# Outputs.net
KiCad netlist of a schematic drawn in Altium Designer
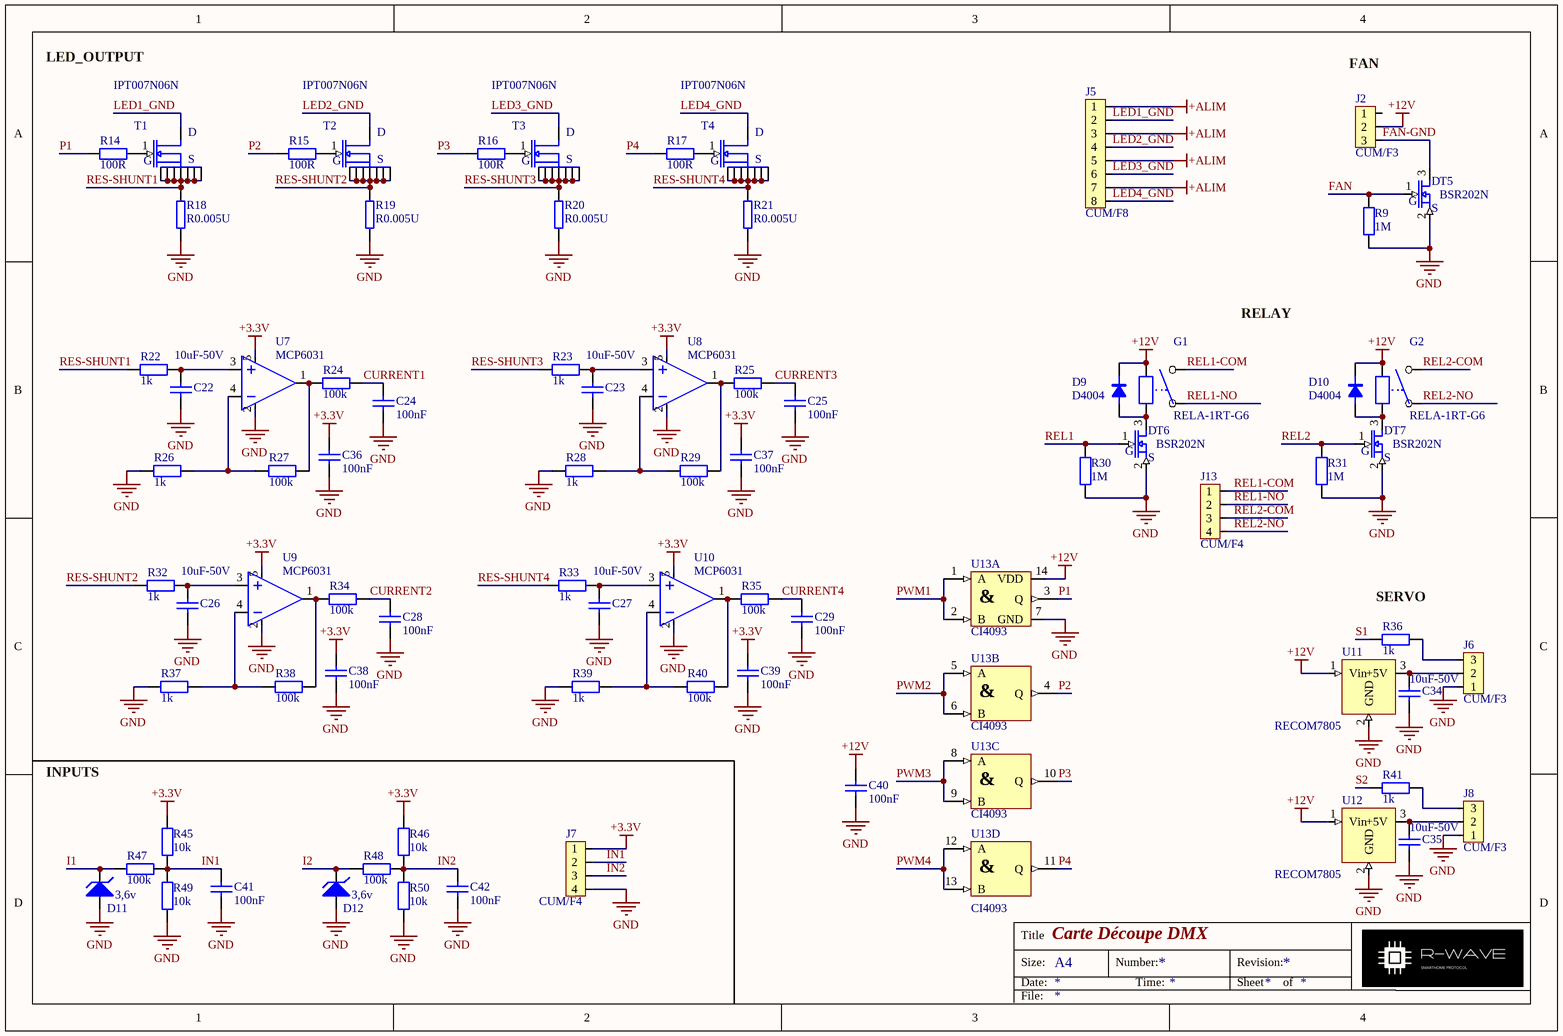
[diagram p0: Outputs.SchDoc]

(export (version "E")
  (design (tool "Eeschema 10.0.6"))
  (components
    (comp (ref "C22")
      (value "10uF-50V")
      (footprint "C1206")
      (description "Capacitor")
      (libsource (lib "MyLibrary") (part "Cap"))
    )
    (comp (ref "C23")
      (value "10uF-50V")
      (footprint "C1206")
      (description "Capacitor")
      (libsource (lib "MyLibrary") (part "Cap"))
    )
    (comp (ref "C24")
      (value "100nF")
      (footprint "C0603")
      (description "Capacitor")
      (libsource (lib "MyLibrary") (part "Cap"))
    )
    (comp (ref "C25")
      (value "100nF")
      (footprint "C0603")
      (description "Capacitor")
      (libsource (lib "MyLibrary") (part "Cap"))
    )
    (comp (ref "C26")
      (value "10uF-50V")
      (footprint "C1206")
      (description "Capacitor")
      (libsource (lib "MyLibrary") (part "Cap"))
    )
    (comp (ref "C27")
      (value "10uF-50V")
      (footprint "C1206")
      (description "Capacitor")
      (libsource (lib "MyLibrary") (part "Cap"))
    )
    (comp (ref "C28")
      (value "100nF")
      (footprint "C0603")
      (description "Capacitor")
      (libsource (lib "MyLibrary") (part "Cap"))
    )
    (comp (ref "C29")
      (value "100nF")
      (footprint "C0603")
      (description "Capacitor")
      (libsource (lib "MyLibrary") (part "Cap"))
    )
    (comp (ref "C34")
      (value "10uF-50V")
      (footprint "C1206")
      (description "Capacitor")
      (libsource (lib "MyLibrary") (part "Cap"))
    )
    (comp (ref "C35")
      (value "10uF-50V")
      (footprint "C1206")
      (description "Capacitor")
      (libsource (lib "MyLibrary") (part "Cap"))
    )
    (comp (ref "C36")
      (value "100nF")
      (footprint "C0603")
      (description "Capacitor")
      (libsource (lib "MyLibrary") (part "Cap"))
    )
    (comp (ref "C37")
      (value "100nF")
      (footprint "C0603")
      (description "Capacitor")
      (libsource (lib "MyLibrary") (part "Cap"))
    )
    (comp (ref "C38")
      (value "100nF")
      (footprint "C0603")
      (description "Capacitor")
      (libsource (lib "MyLibrary") (part "Cap"))
    )
    (comp (ref "C39")
      (value "100nF")
      (footprint "C0603")
      (description "Capacitor")
      (libsource (lib "MyLibrary") (part "Cap"))
    )
    (comp (ref "C40")
      (value "100nF")
      (footprint "C0603")
      (description "Capacitor")
      (libsource (lib "MyLibrary") (part "Cap"))
    )
    (comp (ref "C41")
      (value "100nF")
      (footprint "C0603")
      (description "Capacitor")
      (libsource (lib "MyLibrary") (part "Cap"))
    )
    (comp (ref "C42")
      (value "100nF")
      (footprint "C0603")
      (description "Capacitor")
      (libsource (lib "MyLibrary") (part "Cap"))
    )
    (comp (ref "D9")
      (value "D4004")
      (footprint "DIO4004A")
      (description "DIODE CMS 1A 400V  boitier DO214AC")
      (libsource (lib "PROTEL") (part "D4004"))
    )
    (comp (ref "D10")
      (value "D4004")
      (footprint "DIO4004A")
      (description "DIODE CMS 1A 400V  boitier DO214AC")
      (libsource (lib "PROTEL") (part "D4004"))
    )
    (comp (ref "D11")
      (value "3,6v")
      (footprint "SOD123")
      (description "Zener Diode")
      (libsource (lib "MyLibrary") (part "D Zener"))
    )
    (comp (ref "D12")
      (value "3,6v")
      (footprint "SOD123")
      (description "Zener Diode")
      (libsource (lib "MyLibrary") (part "D Zener"))
    )
    (comp (ref "G1")
      (value "RELA-1RT-G6")
      (footprint "RELG6D1A")
      (description "RELAIS 1RT 12V")
      (libsource (lib "PROTEL") (part "RELA-1RT-G6"))
    )
    (comp (ref "G2")
      (value "RELA-1RT-G6")
      (footprint "RELG6D1A")
      (description "RELAIS 1RT 12V")
      (libsource (lib "PROTEL") (part "RELA-1RT-G6"))
    )
    (comp (ref "J2")
      (value "CUM/F3")
      (footprint "HDR1X3")
      (description "connecteur 3 points")
      (libsource (lib "PROTEL") (part "CUM/F3"))
    )
    (comp (ref "J5")
      (value "CUM/F8")
      (footprint "CNT8C3")
      (description "connecteur 8 points")
      (libsource (lib "PROTEL") (part "CUM/F8"))
    )
    (comp (ref "J6")
      (value "CUM/F3")
      (footprint "HDR1X3")
      (description "connecteur 3 points")
      (libsource (lib "") (part "CUM/F3_1"))
    )
    (comp (ref "J7")
      (value "CUM/F4")
      (footprint "CNT4J")
      (description "connecteur  4 points")
      (libsource (lib "PROTEL") (part "CUM/F4"))
    )
    (comp (ref "J8")
      (value "CUM/F3")
      (footprint "HDR1X3")
      (description "connecteur 3 points")
      (libsource (lib "") (part "CUM/F3_1"))
    )
    (comp (ref "J13")
      (value "CUM/F4")
      (footprint "CNT4F0")
      (description "connecteur  4 points")
      (libsource (lib "PROTEL") (part "CUM/F4"))
    )
    (comp (ref "R9")
      (value "1M")
      (footprint "R0603")
      (description "Thin Metal Film Resistor")
      (libsource (lib "") (part "Res_1"))
    )
    (comp (ref "R14")
      (value "100R")
      (footprint "R0603")
      (description "Thin Metal Film Resistor")
      (libsource (lib "") (part "Res_2"))
    )
    (comp (ref "R15")
      (value "100R")
      (footprint "R0603")
      (description "Thin Metal Film Resistor")
      (libsource (lib "") (part "Res_2"))
    )
    (comp (ref "R16")
      (value "100R")
      (footprint "R0603")
      (description "Thin Metal Film Resistor")
      (libsource (lib "") (part "Res_2"))
    )
    (comp (ref "R17")
      (value "100R")
      (footprint "R0603")
      (description "Thin Metal Film Resistor")
      (libsource (lib "") (part "Res_2"))
    )
    (comp (ref "R18")
      (value "R0.005U")
      (footprint "RCER005")
      (description "Resistance 0.005U 1W 1% CMS BOITIER 2512")
      (libsource (lib "PROTEL") (part "R0.005U"))
    )
    (comp (ref "R19")
      (value "R0.005U")
      (footprint "RCER005")
      (description "Resistance 0.005U 1W 1% CMS BOITIER 2512")
      (libsource (lib "PROTEL") (part "R0.005U"))
    )
    (comp (ref "R20")
      (value "R0.005U")
      (footprint "RCER005")
      (description "Resistance 0.005U 1W 1% CMS BOITIER 2512")
      (libsource (lib "PROTEL") (part "R0.005U"))
    )
    (comp (ref "R21")
      (value "R0.005U")
      (footprint "RCER005")
      (description "Resistance 0.005U 1W 1% CMS BOITIER 2512")
      (libsource (lib "PROTEL") (part "R0.005U"))
    )
    (comp (ref "R22")
      (value "1k")
      (footprint "R0603")
      (description "Thin Metal Film Resistor")
      (libsource (lib "") (part "Res_2"))
    )
    (comp (ref "R23")
      (value "1k")
      (footprint "R0603")
      (description "Thin Metal Film Resistor")
      (libsource (lib "") (part "Res_2"))
    )
    (comp (ref "R24")
      (value "100k")
      (footprint "R0603")
      (description "Thin Metal Film Resistor")
      (libsource (lib "") (part "Res_2"))
    )
    (comp (ref "R25")
      (value "100k")
      (footprint "R0603")
      (description "Thin Metal Film Resistor")
      (libsource (lib "") (part "Res_2"))
    )
    (comp (ref "R26")
      (value "1k")
      (footprint "R0603")
      (description "Thin Metal Film Resistor")
      (libsource (lib "") (part "Res_2"))
    )
    (comp (ref "R27")
      (value "100k")
      (footprint "R0603")
      (description "Thin Metal Film Resistor")
      (libsource (lib "") (part "Res_2"))
    )
    (comp (ref "R28")
      (value "1k")
      (footprint "R0603")
      (description "Thin Metal Film Resistor")
      (libsource (lib "") (part "Res_2"))
    )
    (comp (ref "R29")
      (value "100k")
      (footprint "R0603")
      (description "Thin Metal Film Resistor")
      (libsource (lib "") (part "Res_2"))
    )
    (comp (ref "R30")
      (value "1M")
      (footprint "R0603")
      (description "Thin Metal Film Resistor")
      (libsource (lib "") (part "Res_1"))
    )
    (comp (ref "R31")
      (value "1M")
      (footprint "R0603")
      (description "Thin Metal Film Resistor")
      (libsource (lib "") (part "Res_1"))
    )
    (comp (ref "R32")
      (value "1k")
      (footprint "R0603")
      (description "Thin Metal Film Resistor")
      (libsource (lib "") (part "Res_2"))
    )
    (comp (ref "R33")
      (value "1k")
      (footprint "R0603")
      (description "Thin Metal Film Resistor")
      (libsource (lib "") (part "Res_2"))
    )
    (comp (ref "R34")
      (value "100k")
      (footprint "R0603")
      (description "Thin Metal Film Resistor")
      (libsource (lib "") (part "Res_2"))
    )
    (comp (ref "R35")
      (value "100k")
      (footprint "R0603")
      (description "Thin Metal Film Resistor")
      (libsource (lib "") (part "Res_2"))
    )
    (comp (ref "R36")
      (value "1k")
      (footprint "R0603")
      (description "Thin Metal Film Resistor")
      (libsource (lib "") (part "Res_2"))
    )
    (comp (ref "R37")
      (value "1k")
      (footprint "R0603")
      (description "Thin Metal Film Resistor")
      (libsource (lib "") (part "Res_2"))
    )
    (comp (ref "R38")
      (value "100k")
      (footprint "R0603")
      (description "Thin Metal Film Resistor")
      (libsource (lib "") (part "Res_2"))
    )
    (comp (ref "R39")
      (value "1k")
      (footprint "R0603")
      (description "Thin Metal Film Resistor")
      (libsource (lib "") (part "Res_2"))
    )
    (comp (ref "R40")
      (value "100k")
      (footprint "R0603")
      (description "Thin Metal Film Resistor")
      (libsource (lib "") (part "Res_2"))
    )
    (comp (ref "R41")
      (value "1k")
      (footprint "R0603")
      (description "Thin Metal Film Resistor")
      (libsource (lib "") (part "Res_2"))
    )
    (comp (ref "R45")
      (value "10k")
      (footprint "R0603")
      (description "Thin Metal Film Resistor")
      (libsource (lib "MyLibrary") (part "Res"))
    )
    (comp (ref "R46")
      (value "10k")
      (footprint "R0603")
      (description "Thin Metal Film Resistor")
      (libsource (lib "MyLibrary") (part "Res"))
    )
    (comp (ref "R47")
      (value "100k")
      (footprint "R0603")
      (description "Thin Metal Film Resistor")
      (libsource (lib "") (part "Res_2"))
    )
    (comp (ref "R48")
      (value "100k")
      (footprint "R0603")
      (description "Thin Metal Film Resistor")
      (libsource (lib "") (part "Res_2"))
    )
    (comp (ref "R49")
      (value "10k")
      (footprint "R0603")
      (description "Thin Metal Film Resistor")
      (libsource (lib "MyLibrary") (part "Res"))
    )
    (comp (ref "R50")
      (value "10k")
      (footprint "R0603")
      (description "Thin Metal Film Resistor")
      (libsource (lib "MyLibrary") (part "Res"))
    )
    (comp (ref "T1")
      (value "IPT007N06N")
      (footprint "TRA007")
      (description "TRANSISTOR MOS N")
      (libsource (lib "PROTEL") (part "IPT007N06N"))
    )
    (comp (ref "T2")
      (value "IPT007N06N")
      (footprint "TRA007")
      (description "TRANSISTOR MOS N")
      (libsource (lib "PROTEL") (part "IPT007N06N"))
    )
    (comp (ref "T3")
      (value "IPT007N06N")
      (footprint "TRA007")
      (description "TRANSISTOR MOS N")
      (libsource (lib "PROTEL") (part "IPT007N06N"))
    )
    (comp (ref "T4")
      (value "IPT007N06N")
      (footprint "TRA007")
      (description "TRANSISTOR MOS N")
      (libsource (lib "PROTEL") (part "IPT007N06N"))
    )
    (comp (ref "T5")
      (value "BSR202N")
      (footprint "TRA202")
      (description "TRANSISTOR MOS N")
      (libsource (lib "PROTEL") (part "BSR202N"))
    )
    (comp (ref "T6")
      (value "BSR202N")
      (footprint "TRA202")
      (description "TRANSISTOR MOS N")
      (libsource (lib "PROTEL") (part "BSR202N"))
    )
    (comp (ref "T7")
      (value "BSR202N")
      (footprint "TRA202")
      (description "TRANSISTOR MOS N")
      (libsource (lib "PROTEL") (part "BSR202N"))
    )
    (comp (ref "U7")
      (value "MCP6031")
      (footprint "CIA6031")
      (description "SOT23")
      (libsource (lib "PROTEL") (part "MCP6031"))
    )
    (comp (ref "U8")
      (value "MCP6031")
      (footprint "CIA6031")
      (description "SOT23")
      (libsource (lib "PROTEL") (part "MCP6031"))
    )
    (comp (ref "U9")
      (value "MCP6031")
      (footprint "CIA6031")
      (description "SOT23")
      (libsource (lib "PROTEL") (part "MCP6031"))
    )
    (comp (ref "U10")
      (value "MCP6031")
      (footprint "CIA6031")
      (description "SOT23")
      (libsource (lib "PROTEL") (part "MCP6031"))
    )
    (comp (ref "U11")
      (value "RECOM7805")
      (footprint "REG5VG")
      (description "Régulateur à piquer recom")
      (libsource (lib "PROTEL") (part "RECOM7805"))
    )
    (comp (ref "U12")
      (value "RECOM7805")
      (footprint "REG5VG")
      (description "Régulateur à piquer recom")
      (libsource (lib "PROTEL") (part "RECOM7805"))
    )
    (comp (ref "U13")
      (value "CI4093")
      (footprint "CIL4093")
      (description "Quad NAND gate")
      (libsource (lib "PROTEL") (part "CI4093"))
    )
  )
  (nets
    (net (code "1") (name "+3.3V") (class "Default")
      (node (ref "C36") (pin "2") (pinfunction "2_2") (pintype "passive"))
      (node (ref "C37") (pin "2") (pinfunction "2_2") (pintype "passive"))
      (node (ref "C38") (pin "2") (pinfunction "2_2") (pintype "passive"))
      (node (ref "C39") (pin "2") (pinfunction "2_2") (pintype "passive"))
      (node (ref "J7") (pin "1") (pinfunction "1_1") (pintype "passive"))
      (node (ref "R45") (pin "1") (pinfunction "1_1") (pintype "passive"))
      (node (ref "R46") (pin "1") (pinfunction "1_1") (pintype "passive"))
      (node (ref "U10") (pin "5") (pinfunction "VDD_5") (pintype "power_in"))
      (node (ref "U7") (pin "5") (pinfunction "VDD_5") (pintype "power_in"))
      (node (ref "U8") (pin "5") (pinfunction "VDD_5") (pintype "power_in"))
      (node (ref "U9") (pin "5") (pinfunction "VDD_5") (pintype "power_in"))
    )
    (net (code "2") (name "+12V") (class "Default")
      (node (ref "C40") (pin "2") (pinfunction "2_2") (pintype "passive"))
      (node (ref "D10") (pin "1") (pinfunction "1_1") (pintype "passive"))
      (node (ref "D9") (pin "1") (pinfunction "1_1") (pintype "passive"))
      (node (ref "G1") (pin "7") (pintype "passive"))
      (node (ref "G2") (pin "7") (pintype "passive"))
      (node (ref "J2") (pin "2") (pinfunction "2_2") (pintype "passive"))
      (node (ref "U11") (pin "1") (pinfunction "Vin_1") (pintype "input"))
      (node (ref "U12") (pin "1") (pinfunction "Vin_1") (pintype "input"))
      (node (ref "U13") (pin "14") (pinfunction "VDD_14") (pintype "power_in"))
    )
    (net (code "3") (name "+ALIM") (class "Default")
      (node (ref "J5") (pin "1") (pinfunction "1_1") (pintype "passive"))
      (node (ref "J5") (pin "3") (pinfunction "3_3") (pintype "passive"))
      (node (ref "J5") (pin "5") (pinfunction "5_5") (pintype "passive"))
      (node (ref "J5") (pin "7") (pinfunction "7_7") (pintype "passive"))
    )
    (net (code "4") (name "/CURRENT1") (class "Default")
      (node (ref "C24") (pin "1") (pinfunction "1_1") (pintype "passive"))
      (node (ref "R24") (pin "1") (pinfunction "1_1") (pintype "passive"))
    )
    (net (code "5") (name "/CURRENT2") (class "Default")
      (node (ref "C28") (pin "1") (pinfunction "1_1") (pintype "passive"))
      (node (ref "R34") (pin "1") (pinfunction "1_1") (pintype "passive"))
    )
    (net (code "6") (name "/CURRENT3") (class "Default")
      (node (ref "C25") (pin "1") (pinfunction "1_1") (pintype "passive"))
      (node (ref "R25") (pin "1") (pinfunction "1_1") (pintype "passive"))
    )
    (net (code "7") (name "/CURRENT4") (class "Default")
      (node (ref "C29") (pin "1") (pinfunction "1_1") (pintype "passive"))
      (node (ref "R35") (pin "1") (pinfunction "1_1") (pintype "passive"))
    )
    (net (code "8") (name "/FAN") (class "Default")
      (node (ref "R9") (pin "2") (pinfunction "2_2") (pintype "passive"))
      (node (ref "T5") (pin "1") (pinfunction "G_1") (pintype "input"))
    )
    (net (code "9") (name "/FAN-GND") (class "Default")
      (node (ref "J2") (pin "3") (pinfunction "3_3") (pintype "passive"))
      (node (ref "T5") (pin "3") (pinfunction "D_3") (pintype "passive"))
    )
    (net (code "10") (name "/I1") (class "Default")
      (node (ref "D11") (pin "2") (pinfunction "K_2") (pintype "passive"))
      (node (ref "R47") (pin "2") (pinfunction "2_2") (pintype "passive"))
    )
    (net (code "11") (name "/I2") (class "Default")
      (node (ref "D12") (pin "2") (pinfunction "K_2") (pintype "passive"))
      (node (ref "R48") (pin "2") (pinfunction "2_2") (pintype "passive"))
    )
    (net (code "12") (name "/IN1") (class "Default")
      (node (ref "C41") (pin "2") (pinfunction "2_2") (pintype "passive"))
      (node (ref "J7") (pin "2") (pinfunction "2_2") (pintype "passive"))
      (node (ref "R45") (pin "2") (pinfunction "2_2") (pintype "passive"))
      (node (ref "R47") (pin "1") (pinfunction "1_1") (pintype "passive"))
      (node (ref "R49") (pin "1") (pinfunction "1_1") (pintype "passive"))
    )
    (net (code "13") (name "/IN2") (class "Default")
      (node (ref "C42") (pin "2") (pinfunction "2_2") (pintype "passive"))
      (node (ref "J7") (pin "3") (pinfunction "3_3") (pintype "passive"))
      (node (ref "R46") (pin "2") (pinfunction "2_2") (pintype "passive"))
      (node (ref "R48") (pin "1") (pinfunction "1_1") (pintype "passive"))
      (node (ref "R50") (pin "1") (pinfunction "1_1") (pintype "passive"))
    )
    (net (code "14") (name "/LED1_GND") (class "Default")
      (node (ref "J5") (pin "2") (pinfunction "2_2") (pintype "passive"))
      (node (ref "T1") (pin "9") (pinfunction "9_9") (pintype "passive"))
    )
    (net (code "15") (name "/LED2_GND") (class "Default")
      (node (ref "J5") (pin "4") (pinfunction "4_4") (pintype "passive"))
      (node (ref "T2") (pin "9") (pinfunction "9_9") (pintype "passive"))
    )
    (net (code "16") (name "/LED3_GND") (class "Default")
      (node (ref "J5") (pin "6") (pinfunction "6_6") (pintype "passive"))
      (node (ref "T3") (pin "9") (pinfunction "9_9") (pintype "passive"))
    )
    (net (code "17") (name "/LED4_GND") (class "Default")
      (node (ref "J5") (pin "8") (pinfunction "8_8") (pintype "passive"))
      (node (ref "T4") (pin "9") (pinfunction "9_9") (pintype "passive"))
    )
    (net (code "18") (name "/P1") (class "Default")
      (node (ref "R14") (pin "2") (pinfunction "2_2") (pintype "passive"))
      (node (ref "U13") (pin "3") (pinfunction "Q_3") (pintype "output"))
    )
    (net (code "19") (name "/P2") (class "Default")
      (node (ref "R15") (pin "2") (pinfunction "2_2") (pintype "passive"))
      (node (ref "U13") (pin "4") (pinfunction "Q_4") (pintype "output"))
    )
    (net (code "20") (name "/P3") (class "Default")
      (node (ref "R16") (pin "2") (pinfunction "2_2") (pintype "passive"))
      (node (ref "U13") (pin "10") (pinfunction "Q_10") (pintype "output"))
    )
    (net (code "21") (name "/P4") (class "Default")
      (node (ref "R17") (pin "2") (pinfunction "2_2") (pintype "passive"))
      (node (ref "U13") (pin "11") (pinfunction "Q_11") (pintype "output"))
    )
    (net (code "22") (name "/PWM1") (class "Default")
      (node (ref "U13") (pin "1") (pinfunction "A_1") (pintype "input"))
      (node (ref "U13") (pin "2") (pinfunction "B_2") (pintype "input"))
    )
    (net (code "23") (name "/PWM2") (class "Default")
      (node (ref "U13") (pin "5") (pinfunction "A_5") (pintype "input"))
      (node (ref "U13") (pin "6") (pinfunction "B_6") (pintype "input"))
    )
    (net (code "24") (name "/PWM3") (class "Default")
      (node (ref "U13") (pin "8") (pinfunction "A_8") (pintype "input"))
      (node (ref "U13") (pin "9") (pinfunction "B_9") (pintype "input"))
    )
    (net (code "25") (name "/PWM4") (class "Default")
      (node (ref "U13") (pin "12") (pinfunction "A_12") (pintype "input"))
      (node (ref "U13") (pin "13") (pinfunction "B_13") (pintype "input"))
    )
    (net (code "26") (name "/REL1") (class "Default")
      (node (ref "R30") (pin "2") (pinfunction "2_2") (pintype "passive"))
      (node (ref "T6") (pin "1") (pinfunction "G_1") (pintype "input"))
    )
    (net (code "27") (name "/REL1-COM") (class "Default")
      (node (ref "G1") (pin "2") (pintype "passive"))
      (node (ref "J13") (pin "1") (pinfunction "1_1") (pintype "passive"))
    )
    (net (code "28") (name "/REL1-NO") (class "Default")
      (node (ref "G1") (pin "3") (pintype "passive"))
      (node (ref "J13") (pin "2") (pinfunction "2_2") (pintype "passive"))
    )
    (net (code "29") (name "/REL2") (class "Default")
      (node (ref "R31") (pin "2") (pinfunction "2_2") (pintype "passive"))
      (node (ref "T7") (pin "1") (pinfunction "G_1") (pintype "input"))
    )
    (net (code "30") (name "/REL2-COM") (class "Default")
      (node (ref "G2") (pin "2") (pintype "passive"))
      (node (ref "J13") (pin "3") (pinfunction "3_3") (pintype "passive"))
    )
    (net (code "31") (name "/REL2-NO") (class "Default")
      (node (ref "G2") (pin "3") (pintype "passive"))
      (node (ref "J13") (pin "4") (pinfunction "4_4") (pintype "passive"))
    )
    (net (code "32") (name "/RES-SHUNT1") (class "Default")
      (node (ref "R18") (pin "2") (pintype "passive"))
      (node (ref "R22") (pin "2") (pinfunction "2_2") (pintype "passive"))
      (node (ref "T1") (pin "2") (pinfunction "2_2") (pintype "passive"))
      (node (ref "T1") (pin "3") (pinfunction "3_3") (pintype "passive"))
      (node (ref "T1") (pin "4") (pinfunction "4_4") (pintype "passive"))
      (node (ref "T1") (pin "5") (pinfunction "5_5") (pintype "passive"))
      (node (ref "T1") (pin "6") (pinfunction "6_6") (pintype "passive"))
      (node (ref "T1") (pin "7") (pinfunction "7_7") (pintype "passive"))
      (node (ref "T1") (pin "8") (pinfunction "8_8") (pintype "passive"))
    )
    (net (code "33") (name "/RES-SHUNT2") (class "Default")
      (node (ref "R19") (pin "2") (pintype "passive"))
      (node (ref "R32") (pin "2") (pinfunction "2_2") (pintype "passive"))
      (node (ref "T2") (pin "2") (pinfunction "2_2") (pintype "passive"))
      (node (ref "T2") (pin "3") (pinfunction "3_3") (pintype "passive"))
      (node (ref "T2") (pin "4") (pinfunction "4_4") (pintype "passive"))
      (node (ref "T2") (pin "5") (pinfunction "5_5") (pintype "passive"))
      (node (ref "T2") (pin "6") (pinfunction "6_6") (pintype "passive"))
      (node (ref "T2") (pin "7") (pinfunction "7_7") (pintype "passive"))
      (node (ref "T2") (pin "8") (pinfunction "8_8") (pintype "passive"))
    )
    (net (code "34") (name "/RES-SHUNT3") (class "Default")
      (node (ref "R20") (pin "2") (pintype "passive"))
      (node (ref "R23") (pin "2") (pinfunction "2_2") (pintype "passive"))
      (node (ref "T3") (pin "2") (pinfunction "2_2") (pintype "passive"))
      (node (ref "T3") (pin "3") (pinfunction "3_3") (pintype "passive"))
      (node (ref "T3") (pin "4") (pinfunction "4_4") (pintype "passive"))
      (node (ref "T3") (pin "5") (pinfunction "5_5") (pintype "passive"))
      (node (ref "T3") (pin "6") (pinfunction "6_6") (pintype "passive"))
      (node (ref "T3") (pin "7") (pinfunction "7_7") (pintype "passive"))
      (node (ref "T3") (pin "8") (pinfunction "8_8") (pintype "passive"))
    )
    (net (code "35") (name "/RES-SHUNT4") (class "Default")
      (node (ref "R21") (pin "2") (pintype "passive"))
      (node (ref "R33") (pin "2") (pinfunction "2_2") (pintype "passive"))
      (node (ref "T4") (pin "2") (pinfunction "2_2") (pintype "passive"))
      (node (ref "T4") (pin "3") (pinfunction "3_3") (pintype "passive"))
      (node (ref "T4") (pin "4") (pinfunction "4_4") (pintype "passive"))
      (node (ref "T4") (pin "5") (pinfunction "5_5") (pintype "passive"))
      (node (ref "T4") (pin "6") (pinfunction "6_6") (pintype "passive"))
      (node (ref "T4") (pin "7") (pinfunction "7_7") (pintype "passive"))
      (node (ref "T4") (pin "8") (pinfunction "8_8") (pintype "passive"))
    )
    (net (code "36") (name "/S1") (class "Default")
      (node (ref "R36") (pin "2") (pinfunction "2_2") (pintype "passive"))
    )
    (net (code "37") (name "/S2") (class "Default")
      (node (ref "R41") (pin "2") (pinfunction "2_2") (pintype "passive"))
    )
    (net (code "38") (name "GND") (class "Default")
      (node (ref "C22") (pin "1") (pinfunction "1_1") (pintype "passive"))
      (node (ref "C23") (pin "1") (pinfunction "1_1") (pintype "passive"))
      (node (ref "C24") (pin "2") (pinfunction "2_2") (pintype "passive"))
      (node (ref "C25") (pin "2") (pinfunction "2_2") (pintype "passive"))
      (node (ref "C26") (pin "1") (pinfunction "1_1") (pintype "passive"))
      (node (ref "C27") (pin "1") (pinfunction "1_1") (pintype "passive"))
      (node (ref "C28") (pin "2") (pinfunction "2_2") (pintype "passive"))
      (node (ref "C29") (pin "2") (pinfunction "2_2") (pintype "passive"))
      (node (ref "C34") (pin "1") (pinfunction "1_1") (pintype "passive"))
      (node (ref "C35") (pin "1") (pinfunction "1_1") (pintype "passive"))
      (node (ref "C36") (pin "1") (pinfunction "1_1") (pintype "passive"))
      (node (ref "C37") (pin "1") (pinfunction "1_1") (pintype "passive"))
      (node (ref "C38") (pin "1") (pinfunction "1_1") (pintype "passive"))
      (node (ref "C39") (pin "1") (pinfunction "1_1") (pintype "passive"))
      (node (ref "C40") (pin "1") (pinfunction "1_1") (pintype "passive"))
      (node (ref "C41") (pin "1") (pinfunction "1_1") (pintype "passive"))
      (node (ref "C42") (pin "1") (pinfunction "1_1") (pintype "passive"))
      (node (ref "D11") (pin "1") (pinfunction "A_1") (pintype "passive"))
      (node (ref "D12") (pin "1") (pinfunction "A_1") (pintype "passive"))
      (node (ref "J6") (pin "1") (pinfunction "1_1") (pintype "passive"))
      (node (ref "J7") (pin "4") (pinfunction "4_4") (pintype "passive"))
      (node (ref "J8") (pin "1") (pinfunction "1_1") (pintype "passive"))
      (node (ref "R18") (pin "1") (pintype "passive"))
      (node (ref "R19") (pin "1") (pintype "passive"))
      (node (ref "R20") (pin "1") (pintype "passive"))
      (node (ref "R21") (pin "1") (pintype "passive"))
      (node (ref "R26") (pin "2") (pinfunction "2_2") (pintype "passive"))
      (node (ref "R28") (pin "2") (pinfunction "2_2") (pintype "passive"))
      (node (ref "R30") (pin "1") (pinfunction "1_1") (pintype "passive"))
      (node (ref "R31") (pin "1") (pinfunction "1_1") (pintype "passive"))
      (node (ref "R37") (pin "2") (pinfunction "2_2") (pintype "passive"))
      (node (ref "R39") (pin "2") (pinfunction "2_2") (pintype "passive"))
      (node (ref "R49") (pin "2") (pinfunction "2_2") (pintype "passive"))
      (node (ref "R50") (pin "2") (pinfunction "2_2") (pintype "passive"))
      (node (ref "R9") (pin "1") (pinfunction "1_1") (pintype "passive"))
      (node (ref "T5") (pin "2") (pinfunction "S_2") (pintype "input"))
      (node (ref "T6") (pin "2") (pinfunction "S_2") (pintype "input"))
      (node (ref "T7") (pin "2") (pinfunction "S_2") (pintype "input"))
      (node (ref "U10") (pin "2") (pinfunction "VSS_2") (pintype "passive"))
      (node (ref "U11") (pin "2") (pinfunction "GND_2") (pintype "input"))
      (node (ref "U12") (pin "2") (pinfunction "GND_2") (pintype "input"))
      (node (ref "U13") (pin "7") (pinfunction "GND_7") (pintype "power_in"))
      (node (ref "U7") (pin "2") (pinfunction "VSS_2") (pintype "passive"))
      (node (ref "U8") (pin "2") (pinfunction "VSS_2") (pintype "passive"))
      (node (ref "U9") (pin "2") (pinfunction "VSS_2") (pintype "passive"))
    )
    (net (code "39") (name "Net-(J6-Pad3)") (class "Default")
      (node (ref "J6") (pin "3") (pinfunction "3_3") (pintype "passive"))
      (node (ref "R36") (pin "1") (pinfunction "1_1") (pintype "passive"))
    )
    (net (code "40") (name "Net-(J8-Pad3)") (class "Default")
      (node (ref "J8") (pin "3") (pinfunction "3_3") (pintype "passive"))
      (node (ref "R41") (pin "1") (pinfunction "1_1") (pintype "passive"))
    )
    (net (code "41") (name "Net-(R14-Pad1)") (class "Default")
      (node (ref "R14") (pin "1") (pinfunction "1_1") (pintype "passive"))
      (node (ref "T1") (pin "1") (pinfunction "1_1") (pintype "input"))
    )
    (net (code "42") (name "Net-(R15-Pad1)") (class "Default")
      (node (ref "R15") (pin "1") (pinfunction "1_1") (pintype "passive"))
      (node (ref "T2") (pin "1") (pinfunction "1_1") (pintype "input"))
    )
    (net (code "43") (name "Net-(R16-Pad1)") (class "Default")
      (node (ref "R16") (pin "1") (pinfunction "1_1") (pintype "passive"))
      (node (ref "T3") (pin "1") (pinfunction "1_1") (pintype "input"))
    )
    (net (code "44") (name "Net-(R17-Pad1)") (class "Default")
      (node (ref "R17") (pin "1") (pinfunction "1_1") (pintype "passive"))
      (node (ref "T4") (pin "1") (pinfunction "1_1") (pintype "input"))
    )
    (net (code "45") (name "Net-(T6-D)") (class "Default")
      (node (ref "D9") (pin "2") (pinfunction "2_2") (pintype "passive"))
      (node (ref "G1") (pin "8") (pintype "passive"))
      (node (ref "T6") (pin "3") (pinfunction "D_3") (pintype "passive"))
    )
    (net (code "46") (name "Net-(T7-D)") (class "Default")
      (node (ref "D10") (pin "2") (pinfunction "2_2") (pintype "passive"))
      (node (ref "G2") (pin "8") (pintype "passive"))
      (node (ref "T7") (pin "3") (pinfunction "D_3") (pintype "passive"))
    )
    (net (code "47") (name "Net-(U7-Vin+)") (class "Default")
      (node (ref "C22") (pin "2") (pinfunction "2_2") (pintype "passive"))
      (node (ref "R22") (pin "1") (pinfunction "1_1") (pintype "passive"))
      (node (ref "U7") (pin "3") (pinfunction "Vin+_3") (pintype "passive"))
    )
    (net (code "48") (name "Net-(U7-Vin-)") (class "Default")
      (node (ref "R26") (pin "1") (pinfunction "1_1") (pintype "passive"))
      (node (ref "R27") (pin "2") (pinfunction "2_2") (pintype "passive"))
      (node (ref "U7") (pin "4") (pinfunction "Vin-_4") (pintype "passive"))
    )
    (net (code "49") (name "Net-(U7-Vout)") (class "Default")
      (node (ref "R24") (pin "2") (pinfunction "2_2") (pintype "passive"))
      (node (ref "R27") (pin "1") (pinfunction "1_1") (pintype "passive"))
      (node (ref "U7") (pin "1") (pinfunction "Vout_1") (pintype "passive"))
    )
    (net (code "50") (name "Net-(U8-Vin+)") (class "Default")
      (node (ref "C23") (pin "2") (pinfunction "2_2") (pintype "passive"))
      (node (ref "R23") (pin "1") (pinfunction "1_1") (pintype "passive"))
      (node (ref "U8") (pin "3") (pinfunction "Vin+_3") (pintype "passive"))
    )
    (net (code "51") (name "Net-(U8-Vin-)") (class "Default")
      (node (ref "R28") (pin "1") (pinfunction "1_1") (pintype "passive"))
      (node (ref "R29") (pin "2") (pinfunction "2_2") (pintype "passive"))
      (node (ref "U8") (pin "4") (pinfunction "Vin-_4") (pintype "passive"))
    )
    (net (code "52") (name "Net-(U8-Vout)") (class "Default")
      (node (ref "R25") (pin "2") (pinfunction "2_2") (pintype "passive"))
      (node (ref "R29") (pin "1") (pinfunction "1_1") (pintype "passive"))
      (node (ref "U8") (pin "1") (pinfunction "Vout_1") (pintype "passive"))
    )
    (net (code "53") (name "Net-(U9-Vin+)") (class "Default")
      (node (ref "C26") (pin "2") (pinfunction "2_2") (pintype "passive"))
      (node (ref "R32") (pin "1") (pinfunction "1_1") (pintype "passive"))
      (node (ref "U9") (pin "3") (pinfunction "Vin+_3") (pintype "passive"))
    )
    (net (code "54") (name "Net-(U9-Vin-)") (class "Default")
      (node (ref "R37") (pin "1") (pinfunction "1_1") (pintype "passive"))
      (node (ref "R38") (pin "2") (pinfunction "2_2") (pintype "passive"))
      (node (ref "U9") (pin "4") (pinfunction "Vin-_4") (pintype "passive"))
    )
    (net (code "55") (name "Net-(U9-Vout)") (class "Default")
      (node (ref "R34") (pin "2") (pinfunction "2_2") (pintype "passive"))
      (node (ref "R38") (pin "1") (pinfunction "1_1") (pintype "passive"))
      (node (ref "U9") (pin "1") (pinfunction "Vout_1") (pintype "passive"))
    )
    (net (code "56") (name "Net-(U10-Vin+)") (class "Default")
      (node (ref "C27") (pin "2") (pinfunction "2_2") (pintype "passive"))
      (node (ref "R33") (pin "1") (pinfunction "1_1") (pintype "passive"))
      (node (ref "U10") (pin "3") (pinfunction "Vin+_3") (pintype "passive"))
    )
    (net (code "57") (name "Net-(U10-Vin-)") (class "Default")
      (node (ref "R39") (pin "1") (pinfunction "1_1") (pintype "passive"))
      (node (ref "R40") (pin "2") (pinfunction "2_2") (pintype "passive"))
      (node (ref "U10") (pin "4") (pinfunction "Vin-_4") (pintype "passive"))
    )
    (net (code "58") (name "Net-(U10-Vout)") (class "Default")
      (node (ref "R35") (pin "2") (pinfunction "2_2") (pintype "passive"))
      (node (ref "R40") (pin "1") (pinfunction "1_1") (pintype "passive"))
      (node (ref "U10") (pin "1") (pinfunction "Vout_1") (pintype "passive"))
    )
    (net (code "59") (name "Net-(U11-+5V)") (class "Default")
      (node (ref "C34") (pin "2") (pinfunction "2_2") (pintype "passive"))
      (node (ref "J6") (pin "2") (pinfunction "2_2") (pintype "passive"))
      (node (ref "U11") (pin "3") (pinfunction "+5V_3") (pintype "power_in"))
    )
    (net (code "60") (name "Net-(U12-+5V)") (class "Default")
      (node (ref "C35") (pin "2") (pinfunction "2_2") (pintype "passive"))
      (node (ref "J8") (pin "2") (pinfunction "2_2") (pintype "passive"))
      (node (ref "U12") (pin "3") (pinfunction "+5V_3") (pintype "power_in"))
    )
    (net (code "61") (name "unconnected-(J2-Pad1)") (class "Default")
      (node (ref "J2") (pin "1") (pinfunction "1_1") (pintype "passive"))
    )
  )
)
